# Microcontrollerr.net
KiCad netlist of a schematic drawn in Altium Designer
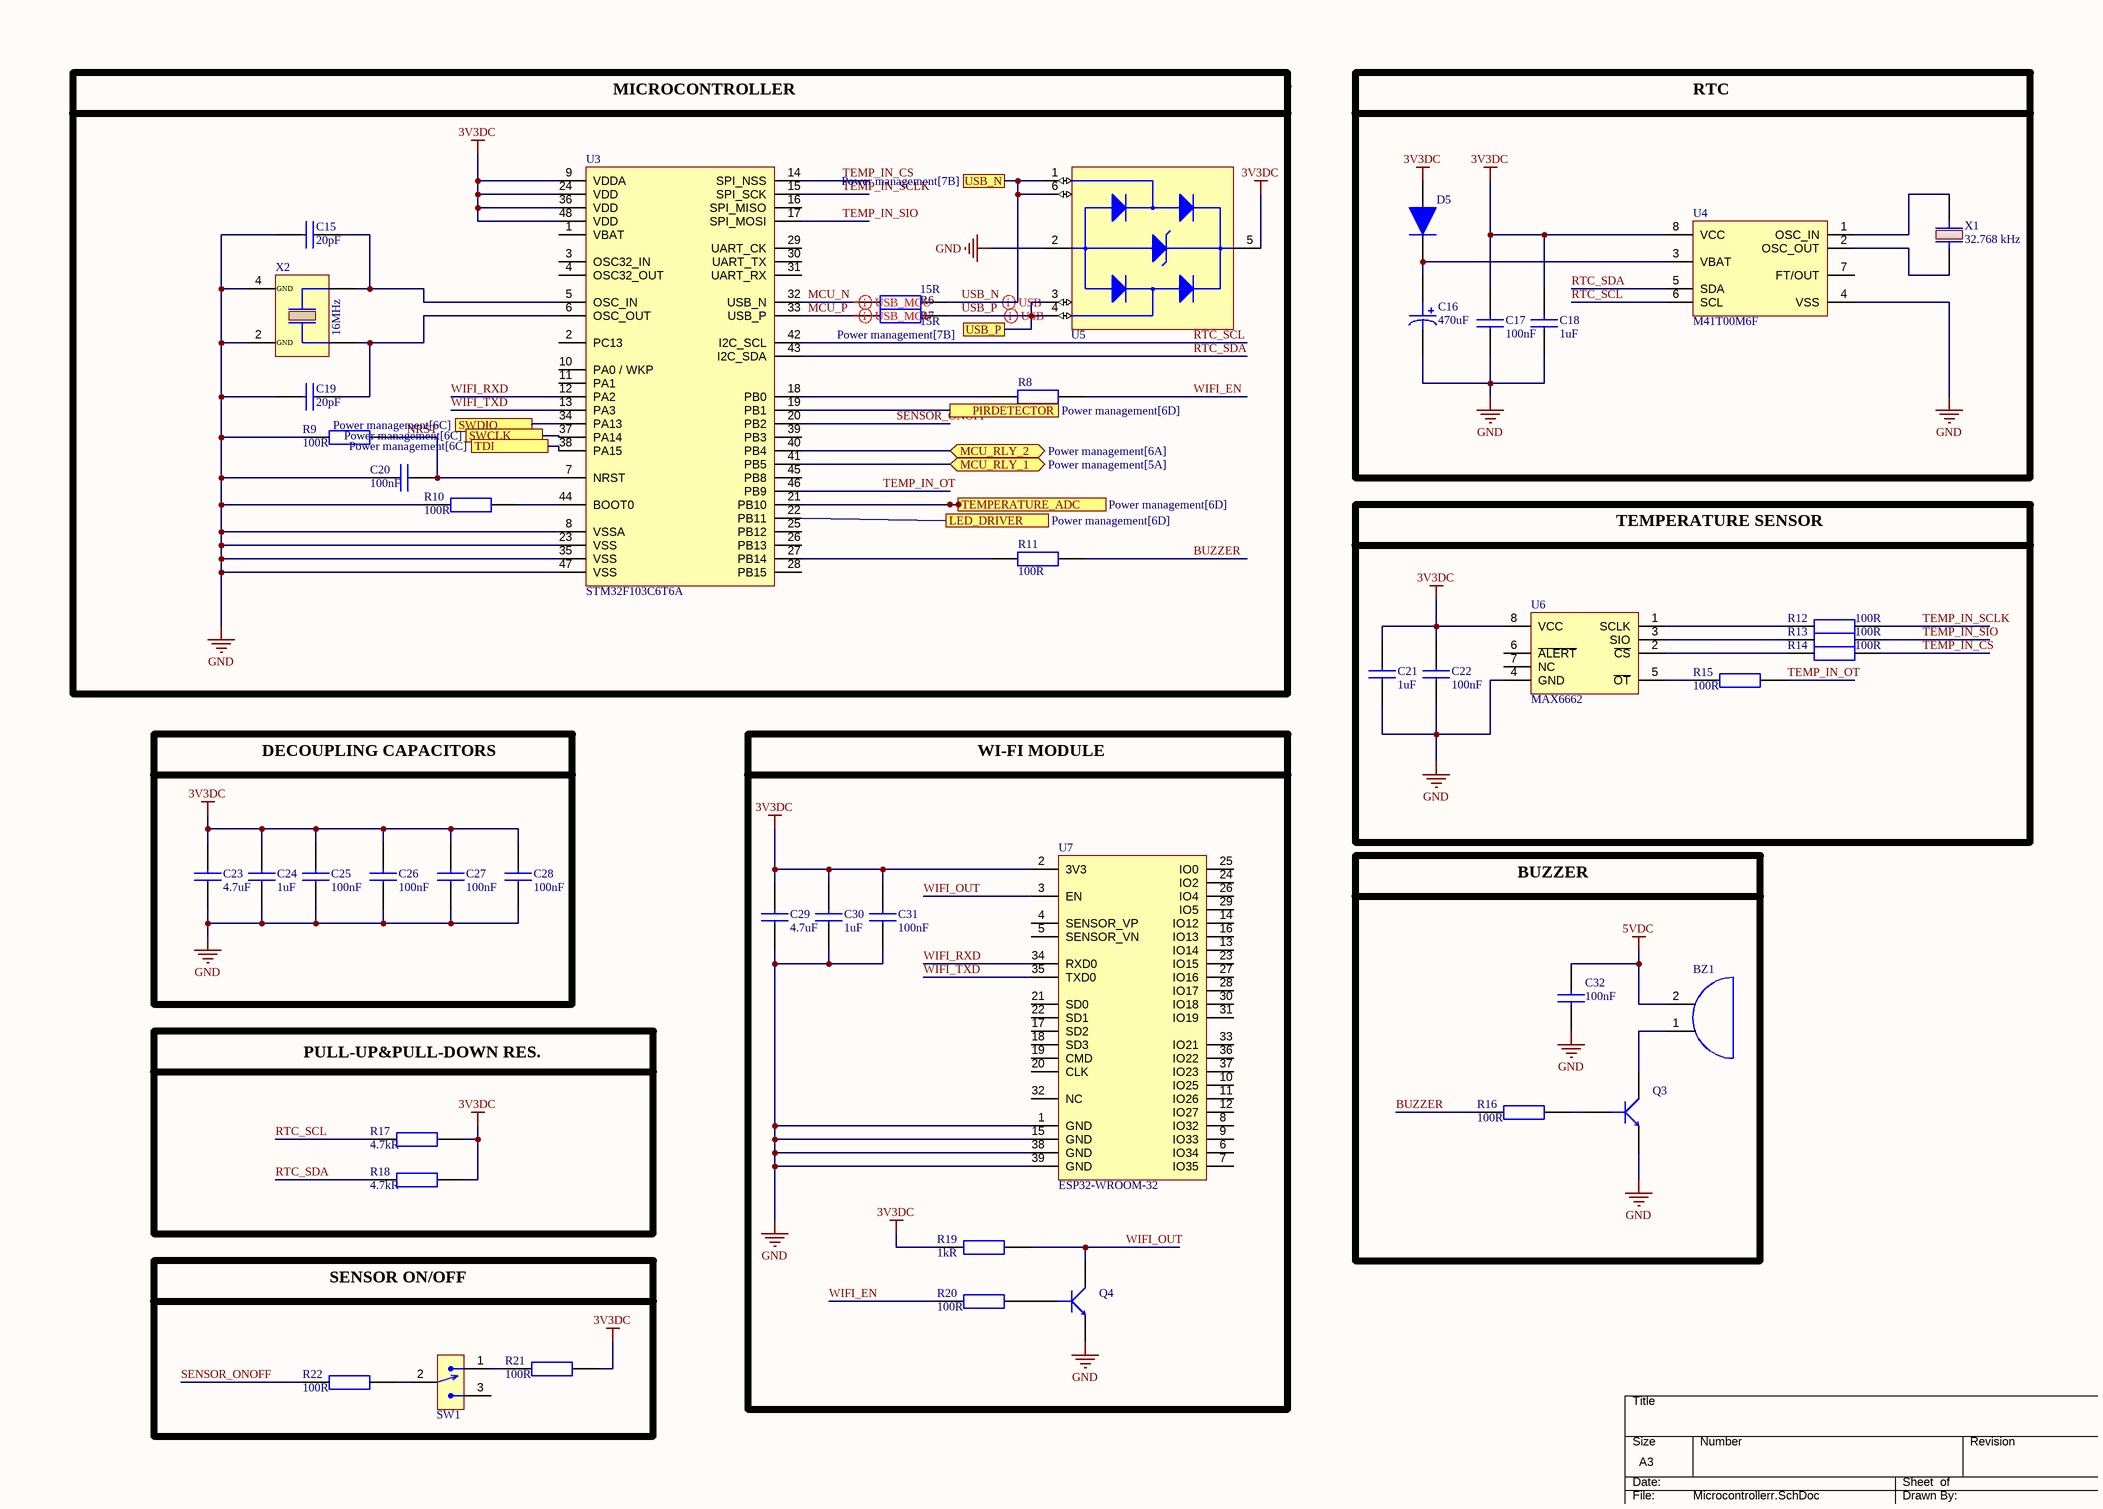
[diagram p0: Microcontrollerr.SchDoc]

(export (version "E")
  (design (tool "Eeschema 10.0.6"))
  (components
    (comp (ref "BZ1")
      (value "CMI-9605IC-0580T")
      (footprint "CMI-9605IC")
      (description "Buzzers Indicator, Internally Driven Magnetic 5V 30mA 2.7kHz 80dB @ 5V, 10cm Through Hole PC Pins")
      (fields (field (name "MANUFACTURER") "CUI Devices") (field (name "DESIGNED BY") "BERK"))
      (libsource (lib "UDEMY_Library") (part "CMI-9605IC-0580T"))
    )
    (comp (ref "C15")
      (value "CL10C200JB8NNNC")
      (footprint "CAP_0603")
      (description "CAP CER 20pF %5 0603 SMD")
      (fields
        (field (name "MANUFACTURER") "Samsung")
        (field (name "TOLERANCE") "5%")
        (field (name "CAPACITANCE") "20pF")
        (field (name "DESIGNED BY") "BERK")
      )
      (libsource (lib "UDEMY_Library") (part "CAP CER 20pF 0603"))
    )
    (comp (ref "C16")
      (value "ESH477M050AH4AA")
      (footprint "CAP_RADIAL_D10_P5")
      (description "CAP ALU ELEC 470uF 50V RADIAL")
      (fields
        (field (name "MANUFACTURER") "KEMET")
        (field (name "TOLERANCE") "20%")
        (field (name "CAPACITANCE") "470uF")
        (field (name "DESIGNED BY") "BERK")
      )
      (libsource (lib "UDEMY_Library") (part "CAP ALU ELEC 470uF 50V"))
    )
    (comp (ref "C17")
      (value "CL21B104KBCNNNC")
      (footprint "CAP_0805")
      (description "CAP CER 100nF %10 0805")
      (fields
        (field (name "MANUFACTURER") "Samsung")
        (field (name "TOLERANCE") "10%")
        (field (name "CAPACITANCE") "100nF")
        (field (name "DESIGNED BY") "BERK")
      )
      (libsource (lib "UDEMY_Library") (part "CAP CER 100nF 0805"))
    )
    (comp (ref "C18")
      (value "CL21B105KBFNNNE")
      (footprint "CAP_0805")
      (description "CAP CER 1uF %10 0805")
      (fields
        (field (name "MANUFACTURER") "Samsung")
        (field (name "TOLERANCE") "10%")
        (field (name "CAPACITANCE") "1uF")
        (field (name "DESIGNED BY") "BERK")
      )
      (libsource (lib "UDEMY_Library") (part "CAP CER 1uF 0805"))
    )
    (comp (ref "C19")
      (value "CL10C200JB8NNNC")
      (footprint "CAP_0603")
      (description "CAP CER 20pF %5 0603 SMD")
      (fields
        (field (name "MANUFACTURER") "Samsung")
        (field (name "TOLERANCE") "5%")
        (field (name "CAPACITANCE") "20pF")
        (field (name "DESIGNED BY") "BERK")
      )
      (libsource (lib "UDEMY_Library") (part "CAP CER 20pF 0603"))
    )
    (comp (ref "C20")
      (value "C0603C104K5RACTU")
      (footprint "CAP_0603")
      (description "CAP CER 100nF %10 0603 SMD")
      (fields
        (field (name "MANUFACTURER") "KEMET")
        (field (name "TOLERANCE") "10%")
        (field (name "CAPACITANCE") "100nF")
        (field (name "DESIGNED BY") "BERK")
      )
      (libsource (lib "UDEMY_Library") (part "CAP CER 100nF 0603"))
    )
    (comp (ref "C21")
      (value "CL21B105KBFNNNE")
      (footprint "CAP_0805")
      (description "CAP CER 1uF %10 0805")
      (fields
        (field (name "MANUFACTURER") "Samsung")
        (field (name "TOLERANCE") "10%")
        (field (name "CAPACITANCE") "1uF")
        (field (name "DESIGNED BY") "BERK")
      )
      (libsource (lib "UDEMY_Library") (part "CAP CER 1uF 0805"))
    )
    (comp (ref "C22")
      (value "CL21B104KBCNNNC")
      (footprint "CAP_0805")
      (description "CAP CER 100nF %10 0805")
      (fields
        (field (name "MANUFACTURER") "Samsung")
        (field (name "TOLERANCE") "10%")
        (field (name "CAPACITANCE") "100nF")
        (field (name "DESIGNED BY") "BERK")
      )
      (libsource (lib "UDEMY_Library") (part "CAP CER 100nF 0805"))
    )
    (comp (ref "C23")
      (value "CL21A475KAQNNNE")
      (footprint "CAP_0805")
      (description "CAP CER 4.7uF %10 0805")
      (fields
        (field (name "MANUFACTURER") "Samsung")
        (field (name "TOLERANCE") "10%")
        (field (name "CAPACITANCE") "4.7uF")
        (field (name "DESIGNED BY") "BERK")
      )
      (libsource (lib "UDEMY_Library") (part "CAP CER 4.7uF 0805"))
    )
    (comp (ref "C24")
      (value "CL21B105KBFNNNE")
      (footprint "CAP_0805")
      (description "CAP CER 1uF %10 0805")
      (fields
        (field (name "MANUFACTURER") "Samsung")
        (field (name "TOLERANCE") "10%")
        (field (name "CAPACITANCE") "1uF")
        (field (name "DESIGNED BY") "BERK")
      )
      (libsource (lib "UDEMY_Library") (part "CAP CER 1uF 0805"))
    )
    (comp (ref "C25")
      (value "C0603C104K5RACTU")
      (footprint "CAP_0603")
      (description "CAP CER 100nF %10 0603 SMD")
      (fields
        (field (name "MANUFACTURER") "KEMET")
        (field (name "TOLERANCE") "10%")
        (field (name "CAPACITANCE") "100nF")
        (field (name "DESIGNED BY") "BERK")
      )
      (libsource (lib "UDEMY_Library") (part "CAP CER 100nF 0603"))
    )
    (comp (ref "C26")
      (value "C0603C104K5RACTU")
      (footprint "CAP_0603")
      (description "CAP CER 100nF %10 0603 SMD")
      (fields
        (field (name "MANUFACTURER") "KEMET")
        (field (name "TOLERANCE") "10%")
        (field (name "CAPACITANCE") "100nF")
        (field (name "DESIGNED BY") "BERK")
      )
      (libsource (lib "UDEMY_Library") (part "CAP CER 100nF 0603"))
    )
    (comp (ref "C27")
      (value "C0603C104K5RACTU")
      (footprint "CAP_0603")
      (description "CAP CER 100nF %10 0603 SMD")
      (fields
        (field (name "MANUFACTURER") "KEMET")
        (field (name "TOLERANCE") "10%")
        (field (name "CAPACITANCE") "100nF")
        (field (name "DESIGNED BY") "BERK")
      )
      (libsource (lib "UDEMY_Library") (part "CAP CER 100nF 0603"))
    )
    (comp (ref "C28")
      (value "C0603C104K5RACTU")
      (footprint "CAP_0603")
      (description "CAP CER 100nF %10 0603 SMD")
      (fields
        (field (name "MANUFACTURER") "KEMET")
        (field (name "TOLERANCE") "10%")
        (field (name "CAPACITANCE") "100nF")
        (field (name "DESIGNED BY") "BERK")
      )
      (libsource (lib "UDEMY_Library") (part "CAP CER 100nF 0603"))
    )
    (comp (ref "C29")
      (value "CL21A475KAQNNNE")
      (footprint "CAP_0805")
      (description "CAP CER 4.7uF %10 0805")
      (fields
        (field (name "MANUFACTURER") "Samsung")
        (field (name "TOLERANCE") "10%")
        (field (name "CAPACITANCE") "4.7uF")
        (field (name "DESIGNED BY") "BERK")
      )
      (libsource (lib "UDEMY_Library") (part "CAP CER 4.7uF 0805"))
    )
    (comp (ref "C30")
      (value "CL21B105KBFNNNE")
      (footprint "CAP_0805")
      (description "CAP CER 1uF %10 0805")
      (fields
        (field (name "MANUFACTURER") "Samsung")
        (field (name "TOLERANCE") "10%")
        (field (name "CAPACITANCE") "1uF")
        (field (name "DESIGNED BY") "BERK")
      )
      (libsource (lib "UDEMY_Library") (part "CAP CER 1uF 0805"))
    )
    (comp (ref "C31")
      (value "CL21B104KBCNNNC")
      (footprint "CAP_0805")
      (description "CAP CER 100nF %10 0805")
      (fields
        (field (name "MANUFACTURER") "Samsung")
        (field (name "TOLERANCE") "10%")
        (field (name "CAPACITANCE") "100nF")
        (field (name "DESIGNED BY") "BERK")
      )
      (libsource (lib "UDEMY_Library") (part "CAP CER 100nF 0805"))
    )
    (comp (ref "C32")
      (value "CL21B104KBCNNNC")
      (footprint "CAP_0805")
      (description "CAP CER 100nF %10 0805")
      (fields
        (field (name "MANUFACTURER") "Samsung")
        (field (name "TOLERANCE") "10%")
        (field (name "CAPACITANCE") "100nF")
        (field (name "DESIGNED BY") "BERK")
      )
      (libsource (lib "UDEMY_Library") (part "CAP CER 100nF 0805"))
    )
    (comp (ref "D5")
      (value "1N4148WS")
      (footprint "SOD323F")
      (description "Diode, Single, 75 V, 150 mA, 1 V, 4 ns")
      (fields
        (field (name "MANUFACTURER") "ON Semiconductor / Fairchild")
        (field (name "DESIGNED BY") "BERK")
      )
      (libsource (lib "UDEMY_Library") (part "1N4148WS"))
    )
    (comp (ref "Q3")
      (value "MMBT3904-7-F")
      (footprint "SOT-23F")
      (description "Transistor General Purpose BJT NPN 40 Volt 0.2A Automotive 3-Pin SOT-23")
      (fields (field (name "MANUFACTURER") "Diodes Zetex") (field (name "DESIGNED BY") "BERK"))
      (libsource (lib "UDEMY_Library") (part "MMBT3904-7-F"))
    )
    (comp (ref "Q4")
      (value "MMBT3904-7-F")
      (footprint "SOT-23F")
      (description "Transistor General Purpose BJT NPN 40 Volt 0.2A Automotive 3-Pin SOT-23")
      (fields (field (name "MANUFACTURER") "Diodes Zetex") (field (name "DESIGNED BY") "BERK"))
      (libsource (lib "UDEMY_Library") (part "MMBT3904-7-F"))
    )
    (comp (ref "R6")
      (value "RC0603JR-0715RL")
      (footprint "RES_0603")
      (description "RES 15 %5 OHM 0603 SMD")
      (fields
        (field (name "MANUFACTURER") "Yageo")
        (field (name "TOLERANCE") "5%")
        (field (name "RESISTANCE") "15R")
        (field (name "DESIGNED BY") "BERK")
      )
      (libsource (lib "UDEMY_Library") (part "RES 15 OHM 0603"))
    )
    (comp (ref "R7")
      (value "RC0603JR-0715RL")
      (footprint "RES_0603")
      (description "RES 15 %5 OHM 0603 SMD")
      (fields
        (field (name "MANUFACTURER") "Yageo")
        (field (name "TOLERANCE") "5%")
        (field (name "RESISTANCE") "15R")
        (field (name "DESIGNED BY") "BERK")
      )
      (libsource (lib "UDEMY_Library") (part "RES 15 OHM 0603"))
    )
    (comp (ref "R8")
      (value "RC0603JR-07100RL")
      (footprint "RES_0603")
      (description "RES 100 %5 OHM 0603 SMD")
      (fields
        (field (name "MANUFACTURER") "Yageo")
        (field (name "TOLERANCE") "5%")
        (field (name "RESISTANCE") "100R")
        (field (name "DESIGNED BY") "BERK")
      )
      (libsource (lib "UDEMY_Library") (part "RES 100 OHM 0603"))
    )
    (comp (ref "R9")
      (value "RC0603JR-07100RL")
      (footprint "RES_0603")
      (description "RES 100 %5 OHM 0603 SMD")
      (fields
        (field (name "MANUFACTURER") "Yageo")
        (field (name "TOLERANCE") "5%")
        (field (name "RESISTANCE") "100R")
        (field (name "DESIGNED BY") "BERK")
      )
      (libsource (lib "UDEMY_Library") (part "RES 100 OHM 0603"))
    )
    (comp (ref "R10")
      (value "RC0603JR-07100RL")
      (footprint "RES_0603")
      (description "RES 100 %5 OHM 0603 SMD")
      (fields
        (field (name "MANUFACTURER") "Yageo")
        (field (name "TOLERANCE") "5%")
        (field (name "RESISTANCE") "100R")
        (field (name "DESIGNED BY") "BERK")
      )
      (libsource (lib "UDEMY_Library") (part "RES 100 OHM 0603"))
    )
    (comp (ref "R11")
      (value "RC0603JR-07100RL")
      (footprint "RES_0603")
      (description "RES 100 %5 OHM 0603 SMD")
      (fields
        (field (name "MANUFACTURER") "Yageo")
        (field (name "TOLERANCE") "5%")
        (field (name "RESISTANCE") "100R")
        (field (name "DESIGNED BY") "BERK")
      )
      (libsource (lib "UDEMY_Library") (part "RES 100 OHM 0603"))
    )
    (comp (ref "R12")
      (value "RC0603JR-07100RL")
      (footprint "RES_0603")
      (description "RES 100 %5 OHM 0603 SMD")
      (fields
        (field (name "MANUFACTURER") "Yageo")
        (field (name "TOLERANCE") "5%")
        (field (name "RESISTANCE") "100R")
        (field (name "DESIGNED BY") "BERK")
      )
      (libsource (lib "UDEMY_Library") (part "RES 100 OHM 0603"))
    )
    (comp (ref "R13")
      (value "RC0603JR-07100RL")
      (footprint "RES_0603")
      (description "RES 100 %5 OHM 0603 SMD")
      (fields
        (field (name "MANUFACTURER") "Yageo")
        (field (name "TOLERANCE") "5%")
        (field (name "RESISTANCE") "100R")
        (field (name "DESIGNED BY") "BERK")
      )
      (libsource (lib "UDEMY_Library") (part "RES 100 OHM 0603"))
    )
    (comp (ref "R14")
      (value "RC0603JR-07100RL")
      (footprint "RES_0603")
      (description "RES 100 %5 OHM 0603 SMD")
      (fields
        (field (name "MANUFACTURER") "Yageo")
        (field (name "TOLERANCE") "5%")
        (field (name "RESISTANCE") "100R")
        (field (name "DESIGNED BY") "BERK")
      )
      (libsource (lib "UDEMY_Library") (part "RES 100 OHM 0603"))
    )
    (comp (ref "R15")
      (value "RC0603JR-07100RL")
      (footprint "RES_0603")
      (description "RES 100 %5 OHM 0603 SMD")
      (fields
        (field (name "MANUFACTURER") "Yageo")
        (field (name "TOLERANCE") "5%")
        (field (name "RESISTANCE") "100R")
        (field (name "DESIGNED BY") "BERK")
      )
      (libsource (lib "UDEMY_Library") (part "RES 100 OHM 0603"))
    )
    (comp (ref "R16")
      (value "RC0603JR-07100RL")
      (footprint "RES_0603")
      (description "RES 100 %5 OHM 0603 SMD")
      (fields
        (field (name "MANUFACTURER") "Yageo")
        (field (name "TOLERANCE") "5%")
        (field (name "RESISTANCE") "100R")
        (field (name "DESIGNED BY") "BERK")
      )
      (libsource (lib "UDEMY_Library") (part "RES 100 OHM 0603"))
    )
    (comp (ref "R17")
      (value "RC0603JR-074K7L")
      (footprint "RES_0603")
      (description "RES 4K7 %5 OHM 0603 SMD")
      (fields
        (field (name "MANUFACTURER") "Yageo")
        (field (name "TOLERANCE") "5%")
        (field (name "RESISTANCE") "4.7kR")
        (field (name "DESIGNED BY") "BERK")
      )
      (libsource (lib "UDEMY_Library") (part "RES 4K7 OHM 0603"))
    )
    (comp (ref "R18")
      (value "RC0603JR-074K7L")
      (footprint "RES_0603")
      (description "RES 4K7 %5 OHM 0603 SMD")
      (fields
        (field (name "MANUFACTURER") "Yageo")
        (field (name "TOLERANCE") "5%")
        (field (name "RESISTANCE") "4.7kR")
        (field (name "DESIGNED BY") "BERK")
      )
      (libsource (lib "UDEMY_Library") (part "RES 4K7 OHM 0603"))
    )
    (comp (ref "R19")
      (value "RC0603FR-0710KL")
      (footprint "RES_0603")
      (description "RES 1K %1 OHM 0603 SMD")
      (fields
        (field (name "MANUFACTURER") "Yageo")
        (field (name "MANUFACTURER PART NUMBER") "RC0603JR-071KL")
        (field (name "RESISTANCE") "1kR")
        (field (name "DESIGNED BY") "BERK")
      )
      (libsource (lib "UDEMY_Library") (part "RES 1K OHM 0603"))
    )
    (comp (ref "R20")
      (value "RC0603JR-07100RL")
      (footprint "RES_0603")
      (description "RES 100 %5 OHM 0603 SMD")
      (fields
        (field (name "MANUFACTURER") "Yageo")
        (field (name "TOLERANCE") "5%")
        (field (name "RESISTANCE") "100R")
        (field (name "DESIGNED BY") "BERK")
      )
      (libsource (lib "UDEMY_Library") (part "RES 100 OHM 0603"))
    )
    (comp (ref "R21")
      (value "RC0603JR-07100RL")
      (footprint "RES_0603")
      (description "RES 100 %5 OHM 0603 SMD")
      (fields
        (field (name "MANUFACTURER") "Yageo")
        (field (name "TOLERANCE") "5%")
        (field (name "RESISTANCE") "100R")
        (field (name "DESIGNED BY") "BERK")
      )
      (libsource (lib "UDEMY_Library") (part "RES 100 OHM 0603"))
    )
    (comp (ref "R22")
      (value "RC0603JR-07100RL")
      (footprint "RES_0603")
      (description "RES 100 %5 OHM 0603 SMD")
      (fields
        (field (name "MANUFACTURER") "Yageo")
        (field (name "TOLERANCE") "5%")
        (field (name "RESISTANCE") "100R")
        (field (name "DESIGNED BY") "BERK")
      )
      (libsource (lib "") (part "RES 100 OHM 0603_1"))
    )
    (comp (ref "SW1")
      (value "EG1215AA")
      (footprint "EG1215AA")
      (description "Slide Switch, SPDT, 0.025A, 24V, SMD")
      (fields
        (field (name "MANUFACTURER") "E-Switch")
        (field (name "TOLERANCE") "4.95%")
        (field (name "DESIGNED BY") "BERK")
      )
      (libsource (lib "UDEMY_Library") (part "EG1215AA"))
    )
    (comp (ref "U3")
      (value "STM32F103C6T6A")
      (footprint "LQFP-48")
      (description "MCU 32-bit STM32F ARM Cortex M3 RISC 32KB Flash 2.5V/3.3V 48-Pin LQFP Tray")
      (fields (field (name "MANUFACTURER") "STMicroelectronics") (field (name "DESIGNED BY") "BERK"))
      (libsource (lib "UDEMY_Library") (part "STM32F103C6T6A"))
    )
    (comp (ref "U4")
      (value "M41T00M6F")
      (footprint "SOIC8")
      (description "IC RTC CLK/CALENDAR I2C 8-SOIC")
      (fields (field (name "MANUFACTURER") "STMicroelectronics") (field (name "DESIGNED BY") "BERK"))
      (libsource (lib "UDEMY_Library") (part "M41T00M6F"))
    )
    (comp (ref "U5")
      (value "USBLC6-2SC6")
      (footprint "SOT23-6L")
      (description "TVS DIODE 5.25V 17V SOT23-6")
      (fields (field (name "MANUFACTURER") "STMicroelectronics") (field (name "DESIGNED BY") "BERK"))
      (libsource (lib "UDEMY_Library") (part "USB PROTECTION"))
    )
    (comp (ref "U6")
      (value "MAX6662")
      (footprint "SOIC8")
      (description "SENSOR TEMPERATURE SPI 8SOIC")
      (fields
        (field (name "MANUFACTURER") "Maxim")
        (field (name "MANUFACTURER PART NUMBER") "MAX6662MSA+")
        (field (name "DESIGNED BY") "BERK")
      )
      (libsource (lib "UDEMY_Library") (part "MAX6662"))
    )
    (comp (ref "U7")
      (value "ESP32-WROOM-32")
      (footprint "ESP32-32")
      (description "SMD MODULE, ESP32-D0WDQ6, 32MBIT")
      (fields (field (name "MANUFACTURER") "Espressif Systems") (field (name "DESIGNED BY") "BERK"))
      (libsource (lib "UDEMY_Library") (part "ESP32-WROOM-32"))
    )
    (comp (ref "X1")
      (value "ABS05-32.768KHZ-T")
      (footprint "ABS05")
      (description "Crystal, 32.768 kHz, SMD, 1.6mm x 1mm, 12.5 pF, 20 ppm, ABS05 Series")
      (fields
        (field (name "MANUFACTURER") "Abracon")
        (field (name "TOLERANCE") "20ppm")
        (field (name "OPERATING FREQUENCY") "32.768 kHz")
        (field (name "DESIGNED BY") "BERK")
      )
      (libsource (lib "UDEMY_Library") (part "CRYSTAL 32768kHZ"))
    )
    (comp (ref "X2")
      (value "ECS-160-20-30B-TR")
      (footprint "ECS")
      (description "CRYSTAL 16.0000MHZ 20PF SMD")
      (fields
        (field (name "MANUFACTURER") "ECS International")
        (field (name "TOLERANCE") "50ppm")
        (field (name "FREQUENCY") "16MHz")
        (field (name "DESIGNED BY") "BERK")
      )
      (libsource (lib "UDEMY_Library") (part "CRYSTAL 16MHz"))
    )
  )
  (nets
    (net (code "1") (name "/BUZZER") (class "Default")
      (node (ref "R11") (pin "2") (pinfunction "2_2") (pintype "passive"))
      (node (ref "R16") (pin "1") (pinfunction "1_1") (pintype "passive"))
    )
    (net (code "2") (name "/LED_DRIVER") (class "Default")
      (node (ref "U3") (pin "22") (pinfunction "PB11_22") (pintype "passive"))
    )
    (net (code "3") (name "/MCU_N") (class "Default")
      (node (ref "R6") (pin "1") (pinfunction "1_1") (pintype "passive"))
      (node (ref "U3") (pin "32") (pinfunction "USB_N_32") (pintype "passive"))
    )
    (net (code "4") (name "/MCU_P") (class "Default")
      (node (ref "R7") (pin "1") (pinfunction "1_1") (pintype "passive"))
      (node (ref "U3") (pin "33") (pinfunction "USB_P_33") (pintype "passive"))
    )
    (net (code "5") (name "/MCU_RLY_1") (class "Default")
      (node (ref "U3") (pin "41") (pinfunction "PB5_41") (pintype "passive"))
    )
    (net (code "6") (name "/MCU_RLY_2") (class "Default")
      (node (ref "U3") (pin "40") (pinfunction "PB4_40") (pintype "passive"))
    )
    (net (code "7") (name "/NRST") (class "Default")
      (node (ref "C20") (pin "1") (pinfunction "1_1") (pintype "passive"))
      (node (ref "R9") (pin "2") (pinfunction "2_2") (pintype "passive"))
      (node (ref "U3") (pin "7") (pinfunction "NRST_7") (pintype "passive"))
    )
    (net (code "8") (name "/PIRDETECTOR") (class "Default")
      (node (ref "U3") (pin "19") (pinfunction "PB1_19") (pintype "passive"))
    )
    (net (code "9") (name "/RTC_SCL") (class "Default")
      (node (ref "R17") (pin "1") (pinfunction "1_1") (pintype "passive"))
      (node (ref "U3") (pin "42") (pinfunction "I2C_SCL_42") (pintype "passive"))
      (node (ref "U4") (pin "6") (pinfunction "SCL_6") (pintype "passive"))
    )
    (net (code "10") (name "/RTC_SDA") (class "Default")
      (node (ref "R18") (pin "1") (pinfunction "1_1") (pintype "passive"))
      (node (ref "U3") (pin "43") (pinfunction "I2C_SDA_43") (pintype "passive"))
      (node (ref "U4") (pin "5") (pinfunction "SDA_5") (pintype "passive"))
    )
    (net (code "11") (name "/SENSOR_ONOFF") (class "Default")
      (node (ref "R22") (pin "2") (pinfunction "2_2") (pintype "passive"))
      (node (ref "U3") (pin "20") (pinfunction "PB2_20") (pintype "passive"))
    )
    (net (code "12") (name "/SWCLK") (class "Default")
      (node (ref "U3") (pin "37") (pinfunction "PA14_37") (pintype "passive"))
    )
    (net (code "13") (name "/SWDIO") (class "Default")
      (node (ref "U3") (pin "34") (pinfunction "PA13_34") (pintype "passive"))
    )
    (net (code "14") (name "/TDI") (class "Default")
      (node (ref "U3") (pin "38") (pinfunction "PA15_38") (pintype "passive"))
    )
    (net (code "15") (name "/TEMPERATURE_ADC") (class "Default")
      (node (ref "U3") (pin "21") (pinfunction "PB10_21") (pintype "passive"))
    )
    (net (code "16") (name "/TEMP_IN_CS") (class "Default")
      (node (ref "R14") (pin "2") (pinfunction "2_2") (pintype "passive"))
      (node (ref "U3") (pin "14") (pinfunction "SPI_NSS_14") (pintype "passive"))
    )
    (net (code "17") (name "/TEMP_IN_OT") (class "Default")
      (node (ref "R15") (pin "2") (pinfunction "2_2") (pintype "passive"))
      (node (ref "U3") (pin "46") (pinfunction "PB9_46") (pintype "passive"))
    )
    (net (code "18") (name "/TEMP_IN_SCLK") (class "Default")
      (node (ref "R12") (pin "2") (pinfunction "2_2") (pintype "passive"))
      (node (ref "U3") (pin "15") (pinfunction "SPI_SCK_15") (pintype "passive"))
    )
    (net (code "19") (name "/TEMP_IN_SIO") (class "Default")
      (node (ref "R13") (pin "2") (pinfunction "2_2") (pintype "passive"))
      (node (ref "U3") (pin "17") (pinfunction "SPI_MOSI_17") (pintype "passive"))
    )
    (net (code "20") (name "/USB_N") (class "Default")
      (node (ref "R6") (pin "2") (pinfunction "2_2") (pintype "passive"))
      (node (ref "U5") (pin "1") (pinfunction "I/O1_1") (pintype "bidirectional"))
      (node (ref "U5") (pin "6") (pinfunction "I/O1_6") (pintype "bidirectional"))
    )
    (net (code "21") (name "/USB_P") (class "Default")
      (node (ref "R7") (pin "2") (pinfunction "2_2") (pintype "passive"))
      (node (ref "U5") (pin "3") (pinfunction "I/O2_3") (pintype "bidirectional"))
      (node (ref "U5") (pin "4") (pinfunction "I/O2_4") (pintype "bidirectional"))
    )
    (net (code "22") (name "/WIFI_EN") (class "Default")
      (node (ref "R20") (pin "1") (pinfunction "1_1") (pintype "passive"))
      (node (ref "R8") (pin "2") (pinfunction "2_2") (pintype "passive"))
    )
    (net (code "23") (name "/WIFI_OUT") (class "Default")
      (node (ref "Q4") (pin "3") (pinfunction "C_3") (pintype "power_in"))
      (node (ref "R19") (pin "1") (pinfunction "1_1") (pintype "passive"))
      (node (ref "U7") (pin "3") (pinfunction "EN_3") (pintype "passive"))
    )
    (net (code "24") (name "/WIFI_RXD") (class "Default")
      (node (ref "U3") (pin "12") (pinfunction "PA2_12") (pintype "passive"))
      (node (ref "U7") (pin "34") (pinfunction "RXD0_34") (pintype "passive"))
    )
    (net (code "25") (name "/WIFI_TXD") (class "Default")
      (node (ref "U3") (pin "13") (pinfunction "PA3_13") (pintype "passive"))
      (node (ref "U7") (pin "35") (pinfunction "TXD0_35") (pintype "passive"))
    )
    (net (code "26") (name "3V3DC") (class "Default")
      (node (ref "C17") (pin "2") (pinfunction "2_2") (pintype "passive"))
      (node (ref "C18") (pin "2") (pinfunction "2_2") (pintype "passive"))
      (node (ref "C21") (pin "2") (pinfunction "2_2") (pintype "passive"))
      (node (ref "C22") (pin "2") (pinfunction "2_2") (pintype "passive"))
      (node (ref "C23") (pin "2") (pinfunction "2_2") (pintype "passive"))
      (node (ref "C24") (pin "2") (pinfunction "2_2") (pintype "passive"))
      (node (ref "C25") (pin "2") (pinfunction "2_2") (pintype "passive"))
      (node (ref "C26") (pin "2") (pinfunction "2_2") (pintype "passive"))
      (node (ref "C27") (pin "2") (pinfunction "2_2") (pintype "passive"))
      (node (ref "C28") (pin "2") (pinfunction "2_2") (pintype "passive"))
      (node (ref "C29") (pin "2") (pinfunction "2_2") (pintype "passive"))
      (node (ref "C30") (pin "2") (pinfunction "2_2") (pintype "passive"))
      (node (ref "C31") (pin "2") (pinfunction "2_2") (pintype "passive"))
      (node (ref "D5") (pin "2") (pinfunction "2_2") (pintype "power_in"))
      (node (ref "R17") (pin "2") (pinfunction "2_2") (pintype "passive"))
      (node (ref "R18") (pin "2") (pinfunction "2_2") (pintype "passive"))
      (node (ref "R19") (pin "2") (pinfunction "2_2") (pintype "passive"))
      (node (ref "R21") (pin "2") (pinfunction "2_2") (pintype "passive"))
      (node (ref "U3") (pin "24") (pinfunction "VDD_24") (pintype "passive"))
      (node (ref "U3") (pin "36") (pinfunction "VDD_36") (pintype "passive"))
      (node (ref "U3") (pin "48") (pinfunction "VDD_48") (pintype "passive"))
      (node (ref "U3") (pin "9") (pinfunction "VDDA_9") (pintype "passive"))
      (node (ref "U4") (pin "8") (pinfunction "VCC_8") (pintype "passive"))
      (node (ref "U5") (pin "5") (pinfunction "VBUS_5") (pintype "power_in"))
      (node (ref "U6") (pin "8") (pinfunction "VCC_8") (pintype "passive"))
      (node (ref "U7") (pin "2") (pinfunction "3V3_2") (pintype "passive"))
    )
    (net (code "27") (name "5VDC") (class "Default")
      (node (ref "BZ1") (pin "2") (pinfunction "2_2") (pintype "passive"))
      (node (ref "C32") (pin "2") (pinfunction "2_2") (pintype "passive"))
    )
    (net (code "28") (name "GND") (class "Default")
      (node (ref "C15") (pin "2") (pinfunction "2_2") (pintype "passive"))
      (node (ref "C16") (pin "2") (pinfunction "2_2") (pintype "passive"))
      (node (ref "C17") (pin "1") (pinfunction "1_1") (pintype "passive"))
      (node (ref "C18") (pin "1") (pinfunction "1_1") (pintype "passive"))
      (node (ref "C19") (pin "2") (pinfunction "2_2") (pintype "passive"))
      (node (ref "C20") (pin "2") (pinfunction "2_2") (pintype "passive"))
      (node (ref "C21") (pin "1") (pinfunction "1_1") (pintype "passive"))
      (node (ref "C22") (pin "1") (pinfunction "1_1") (pintype "passive"))
      (node (ref "C23") (pin "1") (pinfunction "1_1") (pintype "passive"))
      (node (ref "C24") (pin "1") (pinfunction "1_1") (pintype "passive"))
      (node (ref "C25") (pin "1") (pinfunction "1_1") (pintype "passive"))
      (node (ref "C26") (pin "1") (pinfunction "1_1") (pintype "passive"))
      (node (ref "C27") (pin "1") (pinfunction "1_1") (pintype "passive"))
      (node (ref "C28") (pin "1") (pinfunction "1_1") (pintype "passive"))
      (node (ref "C29") (pin "1") (pinfunction "1_1") (pintype "passive"))
      (node (ref "C30") (pin "1") (pinfunction "1_1") (pintype "passive"))
      (node (ref "C31") (pin "1") (pinfunction "1_1") (pintype "passive"))
      (node (ref "C32") (pin "1") (pinfunction "1_1") (pintype "passive"))
      (node (ref "Q3") (pin "2") (pinfunction "E_2") (pintype "power_in"))
      (node (ref "Q4") (pin "2") (pinfunction "E_2") (pintype "power_in"))
      (node (ref "R10") (pin "1") (pinfunction "1_1") (pintype "passive"))
      (node (ref "R9") (pin "1") (pinfunction "1_1") (pintype "passive"))
      (node (ref "U3") (pin "23") (pinfunction "VSS_23") (pintype "passive"))
      (node (ref "U3") (pin "35") (pinfunction "VSS_35") (pintype "passive"))
      (node (ref "U3") (pin "47") (pinfunction "VSS_47") (pintype "passive"))
      (node (ref "U3") (pin "8") (pinfunction "VSSA_8") (pintype "passive"))
      (node (ref "U4") (pin "4") (pinfunction "VSS_4") (pintype "passive"))
      (node (ref "U5") (pin "2") (pinfunction "GND_2") (pintype "power_in"))
      (node (ref "U6") (pin "4") (pinfunction "GND_4") (pintype "passive"))
      (node (ref "U7") (pin "1") (pinfunction "GND_1") (pintype "passive"))
      (node (ref "U7") (pin "15") (pinfunction "GND_15") (pintype "passive"))
      (node (ref "U7") (pin "38") (pinfunction "GND_38") (pintype "passive"))
      (node (ref "U7") (pin "39") (pinfunction "GND_39") (pintype "passive"))
      (node (ref "X2") (pin "2") (pinfunction "GND_2") (pintype "passive"))
      (node (ref "X2") (pin "4") (pinfunction "GND_4") (pintype "passive"))
    )
    (net (code "29") (name "Net-(Q3-B)") (class "Default")
      (node (ref "Q3") (pin "1") (pinfunction "B_1") (pintype "power_in"))
      (node (ref "R16") (pin "2") (pinfunction "2_2") (pintype "passive"))
    )
    (net (code "30") (name "Net-(Q3-C)") (class "Default")
      (node (ref "BZ1") (pin "1") (pinfunction "1_1") (pintype "passive"))
      (node (ref "Q3") (pin "3") (pinfunction "C_3") (pintype "power_in"))
    )
    (net (code "31") (name "Net-(Q4-B)") (class "Default")
      (node (ref "Q4") (pin "1") (pinfunction "B_1") (pintype "power_in"))
      (node (ref "R20") (pin "2") (pinfunction "2_2") (pintype "passive"))
    )
    (net (code "32") (name "Net-(R21-Pad1)") (class "Default")
      (node (ref "R21") (pin "1") (pinfunction "1_1") (pintype "passive"))
      (node (ref "SW1") (pin "1") (pinfunction "1_1") (pintype "passive"))
    )
    (net (code "33") (name "Net-(R22-Pad1)") (class "Default")
      (node (ref "R22") (pin "1") (pinfunction "1_1") (pintype "passive"))
      (node (ref "SW1") (pin "2") (pinfunction "2_2") (pintype "passive"))
    )
    (net (code "34") (name "Net-(U3-BOOT0)") (class "Default")
      (node (ref "R10") (pin "2") (pinfunction "2_2") (pintype "passive"))
      (node (ref "U3") (pin "44") (pinfunction "BOOT0_44") (pintype "passive"))
    )
    (net (code "35") (name "Net-(U3-OSC_IN)") (class "Default")
      (node (ref "C15") (pin "1") (pinfunction "1_1") (pintype "passive"))
      (node (ref "U3") (pin "5") (pinfunction "OSC_IN_5") (pintype "passive"))
      (node (ref "X2") (pin "3") (pinfunction "3_3") (pintype "passive"))
    )
    (net (code "36") (name "Net-(U3-OSC_OUT)") (class "Default")
      (node (ref "C19") (pin "1") (pinfunction "1_1") (pintype "passive"))
      (node (ref "U3") (pin "6") (pinfunction "OSC_OUT_6") (pintype "passive"))
      (node (ref "X2") (pin "1") (pinfunction "1_1") (pintype "passive"))
    )
    (net (code "37") (name "Net-(U3-PB0)") (class "Default")
      (node (ref "R8") (pin "1") (pinfunction "1_1") (pintype "passive"))
      (node (ref "U3") (pin "18") (pinfunction "PB0_18") (pintype "passive"))
    )
    (net (code "38") (name "Net-(U3-PB14)") (class "Default")
      (node (ref "R11") (pin "1") (pinfunction "1_1") (pintype "passive"))
      (node (ref "U3") (pin "27") (pinfunction "PB14_27") (pintype "passive"))
    )
    (net (code "39") (name "Net-(U4-OSC_IN)") (class "Default")
      (node (ref "U4") (pin "1") (pinfunction "OSC_IN_1") (pintype "passive"))
      (node (ref "X1") (pin "2") (pinfunction "2_2") (pintype "passive"))
    )
    (net (code "40") (name "Net-(U4-OSC_OUT)") (class "Default")
      (node (ref "U4") (pin "2") (pinfunction "OSC_OUT_2") (pintype "passive"))
      (node (ref "X1") (pin "1") (pinfunction "1_1") (pintype "passive"))
    )
    (net (code "41") (name "Net-(U4-VBAT)") (class "Default")
      (node (ref "C16") (pin "1") (pinfunction "1_1") (pintype "passive"))
      (node (ref "D5") (pin "1") (pinfunction "1_1") (pintype "power_in"))
      (node (ref "U4") (pin "3") (pinfunction "VBAT_3") (pintype "passive"))
    )
    (net (code "42") (name "Net-(U6-SCLK)") (class "Default")
      (node (ref "R12") (pin "1") (pinfunction "1_1") (pintype "passive"))
      (node (ref "U6") (pin "1") (pinfunction "SCLK_1") (pintype "passive"))
    )
    (net (code "43") (name "Net-(U6-SIO)") (class "Default")
      (node (ref "R13") (pin "1") (pinfunction "1_1") (pintype "passive"))
      (node (ref "U6") (pin "3") (pinfunction "SIO_3") (pintype "passive"))
    )
    (net (code "44") (name "Net-(U6-~{CS})") (class "Default")
      (node (ref "R14") (pin "1") (pinfunction "1_1") (pintype "passive"))
      (node (ref "U6") (pin "2") (pinfunction "~{CS}_2") (pintype "passive"))
    )
    (net (code "45") (name "Net-(U6-~{OT})") (class "Default")
      (node (ref "R15") (pin "1") (pinfunction "1_1") (pintype "passive"))
      (node (ref "U6") (pin "5") (pinfunction "~{OT}_5") (pintype "passive"))
    )
    (net (code "46") (name "unconnected-(SW1-Pad3)") (class "Default")
      (node (ref "SW1") (pin "3") (pinfunction "3_3") (pintype "passive"))
    )
    (net (code "47") (name "unconnected-(U3-OSC32_IN-Pad3)") (class "Default")
      (node (ref "U3") (pin "3") (pinfunction "OSC32_IN_3") (pintype "passive"))
    )
    (net (code "48") (name "unconnected-(U3-OSC32_OUT-Pad4)") (class "Default")
      (node (ref "U3") (pin "4") (pinfunction "OSC32_OUT_4") (pintype "passive"))
    )
    (net (code "49") (name "unconnected-(U3-PA0_{slash}_WKP-Pad10)") (class "Default")
      (node (ref "U3") (pin "10") (pinfunction "PA0_/_WKP_10") (pintype "passive"))
    )
    (net (code "50") (name "unconnected-(U3-PA1-Pad11)") (class "Default")
      (node (ref "U3") (pin "11") (pinfunction "PA1_11") (pintype "passive"))
    )
    (net (code "51") (name "unconnected-(U3-PB3-Pad39)") (class "Default")
      (node (ref "U3") (pin "39") (pinfunction "PB3_39") (pintype "passive"))
    )
    (net (code "52") (name "unconnected-(U3-PB8-Pad45)") (class "Default")
      (node (ref "U3") (pin "45") (pinfunction "PB8_45") (pintype "passive"))
    )
    (net (code "53") (name "unconnected-(U3-PB12-Pad25)") (class "Default")
      (node (ref "U3") (pin "25") (pinfunction "PB12_25") (pintype "passive"))
    )
    (net (code "54") (name "unconnected-(U3-PB13-Pad26)") (class "Default")
      (node (ref "U3") (pin "26") (pinfunction "PB13_26") (pintype "passive"))
    )
    (net (code "55") (name "unconnected-(U3-PB15-Pad28)") (class "Default")
      (node (ref "U3") (pin "28") (pinfunction "PB15_28") (pintype "passive"))
    )
    (net (code "56") (name "unconnected-(U3-PC13-Pad2)") (class "Default")
      (node (ref "U3") (pin "2") (pinfunction "PC13_2") (pintype "passive"))
    )
    (net (code "57") (name "unconnected-(U3-SPI_MISO-Pad16)") (class "Default")
      (node (ref "U3") (pin "16") (pinfunction "SPI_MISO_16") (pintype "passive"))
    )
    (net (code "58") (name "unconnected-(U3-UART_CK-Pad29)") (class "Default")
      (node (ref "U3") (pin "29") (pinfunction "UART_CK_29") (pintype "passive"))
    )
    (net (code "59") (name "unconnected-(U3-UART_RX-Pad31)") (class "Default")
      (node (ref "U3") (pin "31") (pinfunction "UART_RX_31") (pintype "passive"))
    )
    (net (code "60") (name "unconnected-(U3-UART_TX-Pad30)") (class "Default")
      (node (ref "U3") (pin "30") (pinfunction "UART_TX_30") (pintype "passive"))
    )
    (net (code "61") (name "unconnected-(U3-VBAT-Pad1)") (class "Default")
      (node (ref "U3") (pin "1") (pinfunction "VBAT_1") (pintype "passive"))
    )
    (net (code "62") (name "unconnected-(U4-FT{slash}OUT-Pad7)") (class "Default")
      (node (ref "U4") (pin "7") (pinfunction "FT/OUT_7") (pintype "passive"))
    )
    (net (code "63") (name "unconnected-(U6-NC-Pad7)") (class "Default")
      (node (ref "U6") (pin "7") (pinfunction "NC_7") (pintype "passive"))
    )
    (net (code "64") (name "unconnected-(U6-~{ALERT}-Pad6)") (class "Default")
      (node (ref "U6") (pin "6") (pinfunction "~{ALERT}_6") (pintype "passive"))
    )
    (net (code "65") (name "unconnected-(U7-CLK-Pad20)") (class "Default")
      (node (ref "U7") (pin "20") (pinfunction "CLK_20") (pintype "passive"))
    )
    (net (code "66") (name "unconnected-(U7-CMD-Pad19)") (class "Default")
      (node (ref "U7") (pin "19") (pinfunction "CMD_19") (pintype "passive"))
    )
    (net (code "67") (name "unconnected-(U7-IO0-Pad25)") (class "Default")
      (node (ref "U7") (pin "25") (pinfunction "IO0_25") (pintype "passive"))
    )
    (net (code "68") (name "unconnected-(U7-IO2-Pad24)") (class "Default")
      (node (ref "U7") (pin "24") (pinfunction "IO2_24") (pintype "passive"))
    )
    (net (code "69") (name "unconnected-(U7-IO4-Pad26)") (class "Default")
      (node (ref "U7") (pin "26") (pinfunction "IO4_26") (pintype "passive"))
    )
    (net (code "70") (name "unconnected-(U7-IO5-Pad29)") (class "Default")
      (node (ref "U7") (pin "29") (pinfunction "IO5_29") (pintype "passive"))
    )
    (net (code "71") (name "unconnected-(U7-IO12-Pad14)") (class "Default")
      (node (ref "U7") (pin "14") (pinfunction "IO12_14") (pintype "passive"))
    )
    (net (code "72") (name "unconnected-(U7-IO13-Pad16)") (class "Default")
      (node (ref "U7") (pin "16") (pinfunction "IO13_16") (pintype "passive"))
    )
    (net (code "73") (name "unconnected-(U7-IO14-Pad13)") (class "Default")
      (node (ref "U7") (pin "13") (pinfunction "IO14_13") (pintype "passive"))
    )
    (net (code "74") (name "unconnected-(U7-IO15-Pad23)") (class "Default")
      (node (ref "U7") (pin "23") (pinfunction "IO15_23") (pintype "passive"))
    )
    (net (code "75") (name "unconnected-(U7-IO16-Pad27)") (class "Default")
      (node (ref "U7") (pin "27") (pinfunction "IO16_27") (pintype "passive"))
    )
    (net (code "76") (name "unconnected-(U7-IO17-Pad28)") (class "Default")
      (node (ref "U7") (pin "28") (pinfunction "IO17_28") (pintype "passive"))
    )
    (net (code "77") (name "unconnected-(U7-IO18-Pad30)") (class "Default")
      (node (ref "U7") (pin "30") (pinfunction "IO18_30") (pintype "passive"))
    )
    (net (code "78") (name "unconnected-(U7-IO19-Pad31)") (class "Default")
      (node (ref "U7") (pin "31") (pinfunction "IO19_31") (pintype "passive"))
    )
    (net (code "79") (name "unconnected-(U7-IO21-Pad33)") (class "Default")
      (node (ref "U7") (pin "33") (pinfunction "IO21_33") (pintype "passive"))
    )
    (net (code "80") (name "unconnected-(U7-IO22-Pad36)") (class "Default")
      (node (ref "U7") (pin "36") (pinfunction "IO22_36") (pintype "passive"))
    )
    (net (code "81") (name "unconnected-(U7-IO23-Pad37)") (class "Default")
      (node (ref "U7") (pin "37") (pinfunction "IO23_37") (pintype "passive"))
    )
    (net (code "82") (name "unconnected-(U7-IO25-Pad10)") (class "Default")
      (node (ref "U7") (pin "10") (pinfunction "IO25_10") (pintype "passive"))
    )
    (net (code "83") (name "unconnected-(U7-IO26-Pad11)") (class "Default")
      (node (ref "U7") (pin "11") (pinfunction "IO26_11") (pintype "passive"))
    )
    (net (code "84") (name "unconnected-(U7-IO27-Pad12)") (class "Default")
      (node (ref "U7") (pin "12") (pinfunction "IO27_12") (pintype "passive"))
    )
    (net (code "85") (name "unconnected-(U7-IO32-Pad8)") (class "Default")
      (node (ref "U7") (pin "8") (pinfunction "IO32_8") (pintype "passive"))
    )
    (net (code "86") (name "unconnected-(U7-IO33-Pad9)") (class "Default")
      (node (ref "U7") (pin "9") (pinfunction "IO33_9") (pintype "passive"))
    )
    (net (code "87") (name "unconnected-(U7-IO34-Pad6)") (class "Default")
      (node (ref "U7") (pin "6") (pinfunction "IO34_6") (pintype "passive"))
    )
    (net (code "88") (name "unconnected-(U7-IO35-Pad7)") (class "Default")
      (node (ref "U7") (pin "7") (pinfunction "IO35_7") (pintype "passive"))
    )
    (net (code "89") (name "unconnected-(U7-NC-Pad32)") (class "Default")
      (node (ref "U7") (pin "32") (pinfunction "NC_32") (pintype "passive"))
    )
    (net (code "90") (name "unconnected-(U7-SD0-Pad21)") (class "Default")
      (node (ref "U7") (pin "21") (pinfunction "SD0_21") (pintype "passive"))
    )
    (net (code "91") (name "unconnected-(U7-SD1-Pad22)") (class "Default")
      (node (ref "U7") (pin "22") (pinfunction "SD1_22") (pintype "passive"))
    )
    (net (code "92") (name "unconnected-(U7-SD2-Pad17)") (class "Default")
      (node (ref "U7") (pin "17") (pinfunction "SD2_17") (pintype "passive"))
    )
    (net (code "93") (name "unconnected-(U7-SD3-Pad18)") (class "Default")
      (node (ref "U7") (pin "18") (pinfunction "SD3_18") (pintype "passive"))
    )
    (net (code "94") (name "unconnected-(U7-SENSOR_VN-Pad5)") (class "Default")
      (node (ref "U7") (pin "5") (pinfunction "SENSOR_VN_5") (pintype "passive"))
    )
    (net (code "95") (name "unconnected-(U7-SENSOR_VP-Pad4)") (class "Default")
      (node (ref "U7") (pin "4") (pinfunction "SENSOR_VP_4") (pintype "passive"))
    )
  )
)
